# schematic1.net
KiCad netlist of a schematic drawn in EAGLE
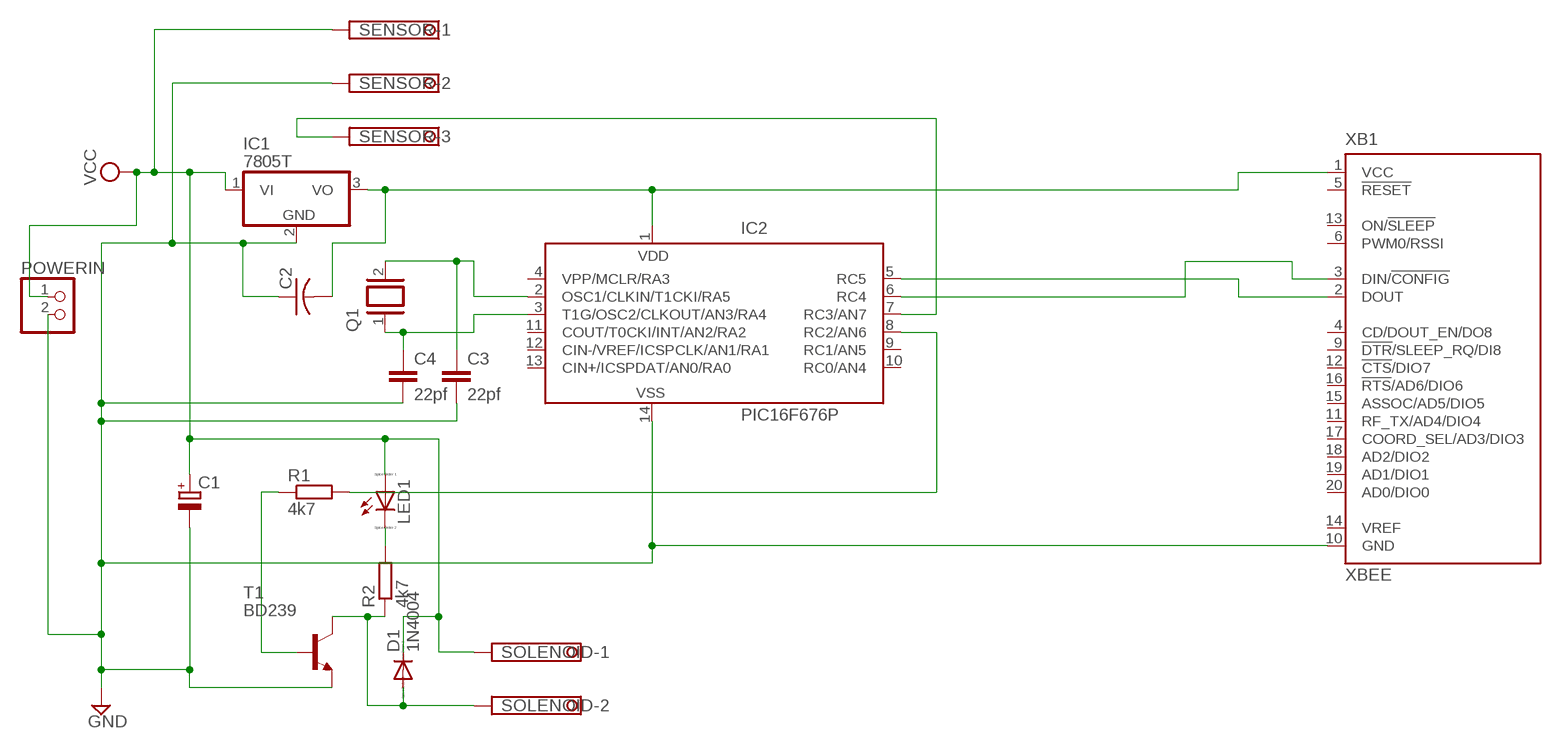
[diagram p0: schematic, sheet 1]

(export (version "E")
  (design (tool "Eeschema 10.0.6"))
  (components
    (comp (ref "C1")
      (value "CPOL-EUE3.5-8")
      (footprint "eagle-import:E3,5-8")
      (libsource (lib "eagle-import") (part "CPOL-EUE3.5-8"))
    )
    (comp (ref "C2")
      (value "C-US050-024X044")
      (footprint "eagle-import:C050-024X044")
      (libsource (lib "eagle-import") (part "C-US050-024X044"))
    )
    (comp (ref "C3")
      (value "22pf")
      (footprint "eagle-import:C025-025X050")
      (libsource (lib "eagle-import") (part "C-EU025-025X050"))
    )
    (comp (ref "C4")
      (value "22pf")
      (footprint "eagle-import:C025-025X050")
      (libsource (lib "eagle-import") (part "C-EU025-025X050"))
    )
    (comp (ref "D1")
      (value "1N4004")
      (footprint "eagle-import:DO41-10")
      (libsource (lib "eagle-import") (part "1N4004"))
    )
    (comp (ref "IC1")
      (value "7805T")
      (footprint "eagle-import:TO220H")
      (libsource (lib "eagle-import") (part "78T05"))
    )
    (comp (ref "IC2")
      (value "PIC16F676P")
      (footprint "eagle-import:DIL14")
      (fields (field (name "MF") "MICROCHIP") (field (name "MPN") "PIC16F676-I/P"))
      (libsource (lib "eagle-import") (part "PIC16F676P"))
    )
    (comp (ref "LED1")
      (value "LED_ELD260")
      (footprint "eagle-import:LED_LD260")
      (libsource (lib "eagle-import") (part "LED_ELD260"))
    )
    (comp (ref "POWERIN")
      (value "PINHD-1X2")
      (footprint "eagle-import:1X02")
      (libsource (lib "eagle-import") (part "PINHD-1X2"))
    )
    (comp (ref "Q1")
      (value "XTAL")
      (footprint "eagle-import:Q")
      (libsource (lib "eagle-import") (part "XTAL"))
    )
    (comp (ref "R1")
      (value "4k7")
      (footprint "eagle-import:0207_15")
      (libsource (lib "eagle-import") (part "R-EU_0207/15"))
    )
    (comp (ref "R2")
      (value "4k7")
      (footprint "eagle-import:0207_15")
      (libsource (lib "eagle-import") (part "R-EU_0207/15"))
    )
    (comp (ref "SENSOR")
      (value "1751251")
      (footprint "eagle-import:1751251")
      (libsource (lib "eagle-import") (part "1751251"))
    )
    (comp (ref "SOLENOID")
      (value "1751248")
      (footprint "eagle-import:1751248")
      (libsource (lib "eagle-import") (part "1751248"))
    )
    (comp (ref "T1")
      (value "BD239")
      (footprint "eagle-import:TO220")
      (libsource (lib "eagle-import") (part "BD239"))
    )
    (comp (ref "XB1")
      (value "XBEE")
      (footprint "eagle-import:XBEE")
      (fields (field (name "MPN") "XBP24-Z7UIT-004"))
      (libsource (lib "eagle-import") (part "XBEE"))
    )
  )
  (nets
    (net (code "1") (name "GND") (class "Default")
      (node (ref "C1") (pin "-") (pinfunction "-_-") (pintype "passive"))
      (node (ref "C2") (pin "1") (pinfunction "1_1") (pintype "passive"))
      (node (ref "C3") (pin "2") (pinfunction "2_2") (pintype "passive"))
      (node (ref "C4") (pin "2") (pinfunction "2_2") (pintype "passive"))
      (node (ref "IC1") (pin "2") (pinfunction "GND_2") (pintype "passive"))
      (node (ref "IC2") (pin "14") (pinfunction "VSS_14") (pintype "power_in"))
      (node (ref "POWERIN") (pin "2") (pinfunction "2_2") (pintype "passive"))
      (node (ref "SENSOR") (pin "2") (pinfunction "K_2") (pintype "passive"))
      (node (ref "T1") (pin "3") (pinfunction "E_3") (pintype "passive"))
      (node (ref "XB1") (pin "10") (pinfunction "GND_10") (pintype "power_in"))
    )
    (net (code "2") (name "Net-(IC1-VO)") (class "Default")
      (node (ref "C2") (pin "2") (pinfunction "2_2") (pintype "passive"))
      (node (ref "IC1") (pin "3") (pinfunction "VO_3") (pintype "passive"))
      (node (ref "IC2") (pin "1") (pinfunction "VDD_1") (pintype "power_in"))
      (node (ref "XB1") (pin "1") (pinfunction "VCC_1") (pintype "power_in"))
    )
    (net (code "3") (name "Net-(IC2-OSC1{slash}CLKIN{slash}T1CKI{slash}RA5)") (class "Default")
      (node (ref "C3") (pin "1") (pinfunction "1_1") (pintype "passive"))
      (node (ref "IC2") (pin "2") (pinfunction "OSC1/CLKIN/T1CKI/RA5_2") (pintype "bidirectional"))
      (node (ref "Q1") (pin "2") (pinfunction "2_2") (pintype "passive"))
    )
    (net (code "4") (name "Net-(IC2-RC2{slash}AN6)") (class "Default")
      (node (ref "IC2") (pin "8") (pinfunction "RC2/AN6_8") (pintype "bidirectional"))
      (node (ref "R1") (pin "2") (pinfunction "2_2") (pintype "passive"))
    )
    (net (code "5") (name "Net-(IC2-RC3{slash}AN7)") (class "Default")
      (node (ref "IC2") (pin "7") (pinfunction "RC3/AN7_7") (pintype "bidirectional"))
      (node (ref "SENSOR") (pin "3") (pinfunction "K_3") (pintype "passive"))
    )
    (net (code "6") (name "Net-(IC2-RC4)") (class "Default")
      (node (ref "IC2") (pin "6") (pinfunction "RC4_6") (pintype "bidirectional"))
      (node (ref "XB1") (pin "3") (pinfunction "DIN/~{CONFIG}_3") (pintype "input"))
    )
    (net (code "7") (name "Net-(IC2-RC5)") (class "Default")
      (node (ref "IC2") (pin "5") (pinfunction "RC5_5") (pintype "bidirectional"))
      (node (ref "XB1") (pin "2") (pinfunction "DOUT_2") (pintype "output"))
    )
    (net (code "8") (name "Net-(IC2-T1G{slash}OSC2{slash}CLKOUT{slash}AN3{slash}RA4)") (class "Default")
      (node (ref "C4") (pin "1") (pinfunction "1_1") (pintype "passive"))
      (node (ref "IC2") (pin "3") (pinfunction "T1G/OSC2/CLKOUT/AN3/RA4_3") (pintype "bidirectional"))
      (node (ref "Q1") (pin "1") (pinfunction "1_1") (pintype "passive"))
    )
    (net (code "9") (name "Net-(LED1-C)") (class "Default")
      (node (ref "LED1") (pin "K") (pinfunction "C_K") (pintype "passive"))
      (node (ref "R2") (pin "2") (pinfunction "2_2") (pintype "passive"))
    )
    (net (code "10") (name "Net-(SOLENOIDB-K)") (class "Default")
      (node (ref "D1") (pin "A") (pinfunction "A_A") (pintype "passive"))
      (node (ref "R2") (pin "1") (pinfunction "1_1") (pintype "passive"))
      (node (ref "SOLENOID") (pin "2") (pinfunction "K_2") (pintype "passive"))
      (node (ref "T1") (pin "2") (pinfunction "C_2") (pintype "passive"))
    )
    (net (code "11") (name "Net-(T1-B)") (class "Default")
      (node (ref "R1") (pin "1") (pinfunction "1_1") (pintype "passive"))
      (node (ref "T1") (pin "1") (pinfunction "B_1") (pintype "passive"))
    )
    (net (code "12") (name "VCC") (class "Default")
      (node (ref "C1") (pin "+") (pinfunction "+_+") (pintype "passive"))
      (node (ref "D1") (pin "C") (pinfunction "C_C") (pintype "passive"))
      (node (ref "IC1") (pin "1") (pinfunction "VI_1") (pintype "input"))
      (node (ref "LED1") (pin "A") (pinfunction "A_A") (pintype "passive"))
      (node (ref "POWERIN") (pin "1") (pinfunction "1_1") (pintype "passive"))
      (node (ref "SENSOR") (pin "1") (pinfunction "K_1") (pintype "passive"))
      (node (ref "SOLENOID") (pin "1") (pinfunction "K_1") (pintype "passive"))
    )
    (net (code "13") (name "unconnected-(IC2-CIN+{slash}ICSPDAT{slash}AN0{slash}RA0-Pad13)") (class "Default")
      (node (ref "IC2") (pin "13") (pinfunction "CIN+/ICSPDAT/AN0/RA0_13") (pintype "bidirectional"))
    )
    (net (code "14") (name "unconnected-(IC2-CIN-{slash}VREF{slash}ICSPCLK{slash}AN1{slash}RA1-Pad12)") (class "Default")
      (node (ref "IC2") (pin "12") (pinfunction "CIN-/VREF/ICSPCLK/AN1/RA1_12") (pintype "bidirectional"))
    )
    (net (code "15") (name "unconnected-(IC2-COUT{slash}T0CKI{slash}INT{slash}AN2{slash}RA2-Pad11)") (class "Default")
      (node (ref "IC2") (pin "11") (pinfunction "COUT/T0CKI/INT/AN2/RA2_11") (pintype "bidirectional"))
    )
    (net (code "16") (name "unconnected-(IC2-RC0{slash}AN4-Pad10)") (class "Default")
      (node (ref "IC2") (pin "10") (pinfunction "RC0/AN4_10") (pintype "bidirectional"))
    )
    (net (code "17") (name "unconnected-(IC2-RC1{slash}AN5-Pad9)") (class "Default")
      (node (ref "IC2") (pin "9") (pinfunction "RC1/AN5_9") (pintype "bidirectional"))
    )
    (net (code "18") (name "unconnected-(IC2-VPP{slash}MCLR{slash}RA3-Pad4)") (class "Default")
      (node (ref "IC2") (pin "4") (pinfunction "VPP/MCLR/RA3_4") (pintype "input"))
    )
    (net (code "19") (name "unconnected-(XB1-AD0{slash}DIO0-Pad20)") (class "Default")
      (node (ref "XB1") (pin "20") (pinfunction "AD0/DIO0_20") (pintype "bidirectional"))
    )
    (net (code "20") (name "unconnected-(XB1-AD1{slash}DIO1-Pad19)") (class "Default")
      (node (ref "XB1") (pin "19") (pinfunction "AD1/DIO1_19") (pintype "bidirectional"))
    )
    (net (code "21") (name "unconnected-(XB1-AD2{slash}DIO2-Pad18)") (class "Default")
      (node (ref "XB1") (pin "18") (pinfunction "AD2/DIO2_18") (pintype "bidirectional"))
    )
    (net (code "22") (name "unconnected-(XB1-ASSOC{slash}AD5{slash}DIO5-Pad15)") (class "Default")
      (node (ref "XB1") (pin "15") (pinfunction "ASSOC/AD5/DIO5_15") (pintype "bidirectional"))
    )
    (net (code "23") (name "unconnected-(XB1-CD{slash}DOUT_EN{slash}DO8-Pad4)") (class "Default")
      (node (ref "XB1") (pin "4") (pinfunction "CD/DOUT_EN/DO8_4") (pintype "output"))
    )
    (net (code "24") (name "unconnected-(XB1-COORD_SEL{slash}AD3{slash}DIO3-Pad17)") (class "Default")
      (node (ref "XB1") (pin "17") (pinfunction "COORD_SEL/AD3/DIO3_17") (pintype "bidirectional"))
    )
    (net (code "25") (name "unconnected-(XB1-ON{slash}~{SLEEP}-Pad13)") (class "Default")
      (node (ref "XB1") (pin "13") (pinfunction "ON/~{SLEEP}_13") (pintype "output"))
    )
    (net (code "26") (name "unconnected-(XB1-PWM0{slash}RSSI-Pad6)") (class "Default")
      (node (ref "XB1") (pin "6") (pinfunction "PWM0/RSSI_6") (pintype "output"))
    )
    (net (code "27") (name "unconnected-(XB1-RF_TX{slash}AD4{slash}DIO4-Pad11)") (class "Default")
      (node (ref "XB1") (pin "11") (pinfunction "RF_TX/AD4/DIO4_11") (pintype "bidirectional"))
    )
    (net (code "28") (name "unconnected-(XB1-VREF-Pad14)") (class "Default")
      (node (ref "XB1") (pin "14") (pinfunction "VREF_14") (pintype "input"))
    )
    (net (code "29") (name "unconnected-(XB1-~{CTS}{slash}DIO7-Pad12)") (class "Default")
      (node (ref "XB1") (pin "12") (pinfunction "~{CTS}/DIO7_12") (pintype "bidirectional"))
    )
    (net (code "30") (name "unconnected-(XB1-~{DTR}{slash}SLEEP_RQ{slash}DI8-Pad9)") (class "Default")
      (node (ref "XB1") (pin "9") (pinfunction "~{DTR}/SLEEP_RQ/DI8_9") (pintype "bidirectional"))
    )
    (net (code "31") (name "unconnected-(XB1-~{RESET}-Pad5)") (class "Default")
      (node (ref "XB1") (pin "5") (pinfunction "~{RESET}_5") (pintype "input"))
    )
    (net (code "32") (name "unconnected-(XB1-~{RTS}{slash}AD6{slash}DIO6-Pad16)") (class "Default")
      (node (ref "XB1") (pin "16") (pinfunction "~{RTS}/AD6/DIO6_16") (pintype "bidirectional"))
    )
  )
)
